# LedClock.net
KiCad netlist of a schematic drawn in EAGLE
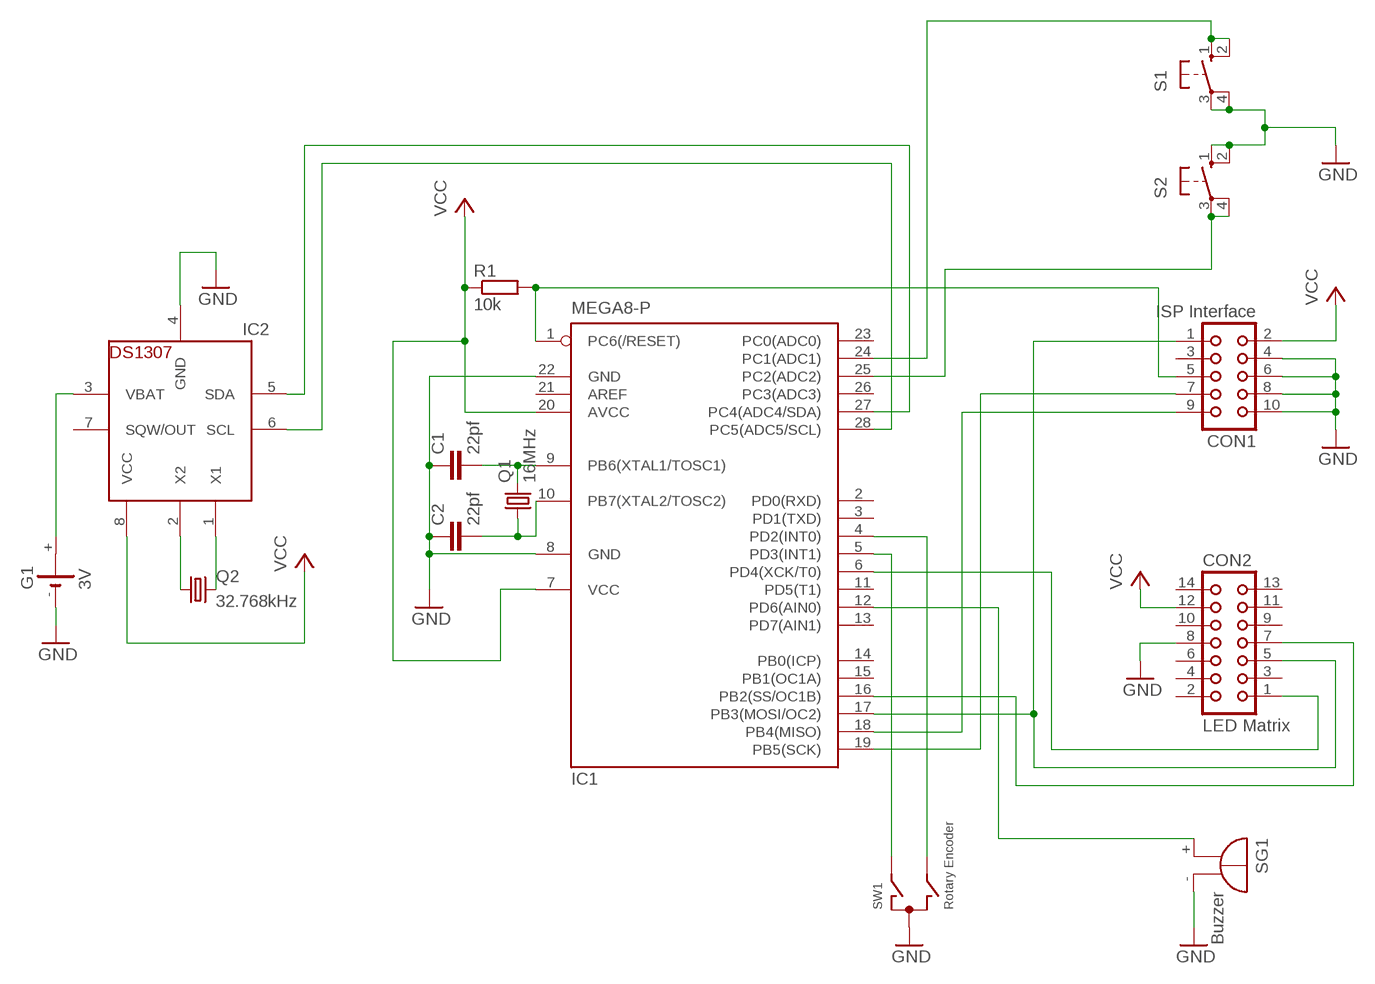
[diagram p0: schematic, sheet 1]

(export (version "E")
  (design (tool "Eeschema 10.0.6"))
  (components
    (comp (ref "C1")
      (value "22pf")
      (footprint "eagle-import:C025-025X050")
      (libsource (lib "eagle-import") (part "C-EU025-025X050"))
    )
    (comp (ref "C2")
      (value "22pf")
      (footprint "eagle-import:C025-025X050")
      (libsource (lib "eagle-import") (part "C-EU025-025X050"))
    )
    (comp (ref "CON1")
      (value "ISP Interface")
      (footprint "eagle-import:CON10")
      (libsource (lib "eagle-import") (part "CON10"))
    )
    (comp (ref "CON2")
      (value "LED Matrix")
      (footprint "eagle-import:CON14L")
      (libsource (lib "eagle-import") (part "CON14L"))
    )
    (comp (ref "G1")
      (value "3V")
      (footprint "eagle-import:CR2032H")
      (libsource (lib "eagle-import") (part "CR2032H"))
    )
    (comp (ref "IC1")
      (value "MEGA8-P")
      (footprint "eagle-import:DIL28-3")
      (libsource (lib "eagle-import") (part "MEGA8-P"))
    )
    (comp (ref "IC2")
      (value "DS1307")
      (footprint "eagle-import:DIL08")
      (libsource (lib "eagle-import") (part "DS1307"))
    )
    (comp (ref "Q1")
      (value "16MHz")
      (footprint "eagle-import:HC49_S")
      (libsource (lib "eagle-import") (part "CRYSTALHC49S"))
    )
    (comp (ref "Q2")
      (value "32.768kHz")
      (footprint "eagle-import:TC38H")
      (libsource (lib "eagle-import") (part "CRYSTALTC38H"))
    )
    (comp (ref "R1")
      (value "10k")
      (footprint "eagle-import:0207_10")
      (libsource (lib "eagle-import") (part "R-EU_0207/10"))
    )
    (comp (ref "S1")
      (value "10-XX")
      (footprint "eagle-import:B3F-10XX")
      (fields (field (name "MPN") "B3F-1000"))
      (libsource (lib "eagle-import") (part "10-XX"))
    )
    (comp (ref "S2")
      (value "10-XX")
      (footprint "eagle-import:B3F-10XX")
      (fields (field (name "MPN") "B3F-1000"))
      (libsource (lib "eagle-import") (part "10-XX"))
    )
    (comp (ref "SG1")
      (value "Buzzer")
      (footprint "eagle-import:EB2209A")
      (libsource (lib "eagle-import") (part "EB2209A"))
    )
    (comp (ref "SW1")
      (value "Rotary Encoder")
      (footprint "eagle-import:ALPS_EC12E_SW")
      (fields (field (name "MPN") "EC12E2424407"))
      (libsource (lib "eagle-import") (part "EC12E_SW"))
    )
  )
  (nets
    (net (code "1") (name "GND") (class "Default")
      (node (ref "C1") (pin "1") (pinfunction "1_1") (pintype "passive"))
      (node (ref "C2") (pin "1") (pinfunction "1_1") (pintype "passive"))
      (node (ref "CON1") (pin "10") (pinfunction "10_10") (pintype "passive"))
      (node (ref "CON1") (pin "4") (pinfunction "4_4") (pintype "passive"))
      (node (ref "CON1") (pin "6") (pinfunction "6_6") (pintype "passive"))
      (node (ref "CON1") (pin "8") (pinfunction "8_8") (pintype "passive"))
      (node (ref "CON2") (pin "8") (pinfunction "8_8") (pintype "passive"))
      (node (ref "G1") (pin "-") (pinfunction "-_-") (pintype "passive"))
      (node (ref "IC1") (pin "22") (pinfunction "GND_22") (pintype "power_in"))
      (node (ref "IC1") (pin "8") (pinfunction "GND_8") (pintype "power_in"))
      (node (ref "IC2") (pin "4") (pinfunction "GND_4") (pintype "power_in"))
      (node (ref "S1") (pin "3") (pinfunction "P_3") (pintype "passive"))
      (node (ref "S1") (pin "4") (pinfunction "P1_4") (pintype "passive"))
      (node (ref "S2") (pin "1") (pinfunction "S_1") (pintype "passive"))
      (node (ref "S2") (pin "2") (pinfunction "S1_2") (pintype "passive"))
      (node (ref "SG1") (pin "-") (pinfunction "-_-") (pintype "passive"))
      (node (ref "SW1") (pin "C") (pinfunction "C_C") (pintype "passive"))
    )
    (net (code "2") (name "Net-(IC1-PB2(SS{slash}OC1B))") (class "Default")
      (node (ref "CON2") (pin "7") (pinfunction "7_7") (pintype "passive"))
      (node (ref "IC1") (pin "16") (pinfunction "PB2(SS/OC1B)_16") (pintype "bidirectional"))
    )
    (net (code "3") (name "Net-(IC1-PB3(MOSI{slash}OC2))") (class "Default")
      (node (ref "CON1") (pin "1") (pinfunction "1_1") (pintype "passive"))
      (node (ref "CON2") (pin "5") (pinfunction "5_5") (pintype "passive"))
      (node (ref "IC1") (pin "17") (pinfunction "PB3(MOSI/OC2)_17") (pintype "bidirectional"))
    )
    (net (code "4") (name "Net-(IC1-PB4(MISO))") (class "Default")
      (node (ref "CON1") (pin "9") (pinfunction "9_9") (pintype "passive"))
      (node (ref "IC1") (pin "18") (pinfunction "PB4(MISO)_18") (pintype "bidirectional"))
    )
    (net (code "5") (name "Net-(IC1-PB5(SCK))") (class "Default")
      (node (ref "CON1") (pin "7") (pinfunction "7_7") (pintype "passive"))
      (node (ref "IC1") (pin "19") (pinfunction "PB5(SCK)_19") (pintype "bidirectional"))
    )
    (net (code "6") (name "Net-(IC1-PB6(XTAL1{slash}TOSC1))") (class "Default")
      (node (ref "C1") (pin "2") (pinfunction "2_2") (pintype "passive"))
      (node (ref "IC1") (pin "9") (pinfunction "PB6(XTAL1/TOSC1)_9") (pintype "bidirectional"))
      (node (ref "Q1") (pin "2") (pinfunction "2_2") (pintype "passive"))
    )
    (net (code "7") (name "Net-(IC1-PB7(XTAL2{slash}TOSC2))") (class "Default")
      (node (ref "C2") (pin "2") (pinfunction "2_2") (pintype "passive"))
      (node (ref "IC1") (pin "10") (pinfunction "PB7(XTAL2/TOSC2)_10") (pintype "bidirectional"))
      (node (ref "Q1") (pin "1") (pinfunction "1_1") (pintype "passive"))
    )
    (net (code "8") (name "Net-(IC1-PC1(ADC1))") (class "Default")
      (node (ref "IC1") (pin "24") (pinfunction "PC1(ADC1)_24") (pintype "bidirectional"))
      (node (ref "S1") (pin "1") (pinfunction "S_1") (pintype "passive"))
      (node (ref "S1") (pin "2") (pinfunction "S1_2") (pintype "passive"))
    )
    (net (code "9") (name "Net-(IC1-PC2(ADC2))") (class "Default")
      (node (ref "IC1") (pin "25") (pinfunction "PC2(ADC2)_25") (pintype "bidirectional"))
      (node (ref "S2") (pin "3") (pinfunction "P_3") (pintype "passive"))
      (node (ref "S2") (pin "4") (pinfunction "P1_4") (pintype "passive"))
    )
    (net (code "10") (name "Net-(IC1-PC4(ADC4{slash}SDA))") (class "Default")
      (node (ref "IC1") (pin "27") (pinfunction "PC4(ADC4/SDA)_27") (pintype "bidirectional"))
      (node (ref "IC2") (pin "5") (pinfunction "SDA_5") (pintype "bidirectional"))
    )
    (net (code "11") (name "Net-(IC1-PC5(ADC5{slash}SCL))") (class "Default")
      (node (ref "IC1") (pin "28") (pinfunction "PC5(ADC5/SCL)_28") (pintype "bidirectional"))
      (node (ref "IC2") (pin "6") (pinfunction "SCL_6") (pintype "bidirectional"))
    )
    (net (code "12") (name "Net-(IC1-PC6({slash}RESET))") (class "Default")
      (node (ref "CON1") (pin "5") (pinfunction "5_5") (pintype "passive"))
      (node (ref "IC1") (pin "1") (pinfunction "PC6(/RESET)_1") (pintype "bidirectional"))
      (node (ref "R1") (pin "2") (pinfunction "2_2") (pintype "passive"))
    )
    (net (code "13") (name "Net-(IC1-PD2(INT0))") (class "Default")
      (node (ref "IC1") (pin "4") (pinfunction "PD2(INT0)_4") (pintype "bidirectional"))
      (node (ref "SW1") (pin "B") (pinfunction "B_B") (pintype "passive"))
    )
    (net (code "14") (name "Net-(IC1-PD3(INT1))") (class "Default")
      (node (ref "IC1") (pin "5") (pinfunction "PD3(INT1)_5") (pintype "bidirectional"))
      (node (ref "SW1") (pin "A") (pinfunction "A_A") (pintype "passive"))
    )
    (net (code "15") (name "Net-(IC1-PD4(XCK{slash}T0))") (class "Default")
      (node (ref "CON2") (pin "1") (pinfunction "1_1") (pintype "passive"))
      (node (ref "IC1") (pin "6") (pinfunction "PD4(XCK/T0)_6") (pintype "bidirectional"))
    )
    (net (code "16") (name "Net-(IC1-PD6(AIN0))") (class "Default")
      (node (ref "IC1") (pin "12") (pinfunction "PD6(AIN0)_12") (pintype "bidirectional"))
      (node (ref "SG1") (pin "+") (pinfunction "+_+") (pintype "passive"))
    )
    (net (code "17") (name "Net-(IC2-VBAT)") (class "Default")
      (node (ref "G1") (pin "+") (pinfunction "+_+") (pintype "passive"))
      (node (ref "IC2") (pin "3") (pinfunction "VBAT_3") (pintype "power_in"))
    )
    (net (code "18") (name "Net-(IC2-X1)") (class "Default")
      (node (ref "IC2") (pin "1") (pinfunction "X1_1") (pintype "passive"))
      (node (ref "Q2") (pin "2") (pinfunction "2_2") (pintype "passive"))
    )
    (net (code "19") (name "Net-(IC2-X2)") (class "Default")
      (node (ref "IC2") (pin "2") (pinfunction "X2_2") (pintype "passive"))
      (node (ref "Q2") (pin "1") (pinfunction "1_1") (pintype "passive"))
    )
    (net (code "20") (name "VCC") (class "Default")
      (node (ref "CON1") (pin "2") (pinfunction "2_2") (pintype "passive"))
      (node (ref "CON2") (pin "12") (pinfunction "12_12") (pintype "passive"))
      (node (ref "IC1") (pin "20") (pinfunction "AVCC_20") (pintype "power_in"))
      (node (ref "IC1") (pin "7") (pinfunction "VCC_7") (pintype "power_in"))
      (node (ref "IC2") (pin "8") (pinfunction "VCC_8") (pintype "power_in"))
      (node (ref "R1") (pin "1") (pinfunction "1_1") (pintype "passive"))
    )
    (net (code "21") (name "unconnected-(CON1-Pad3)") (class "Default")
      (node (ref "CON1") (pin "3") (pinfunction "3_3") (pintype "passive"))
    )
    (net (code "22") (name "unconnected-(CON2-Pad2)") (class "Default")
      (node (ref "CON2") (pin "2") (pinfunction "2_2") (pintype "passive"))
    )
    (net (code "23") (name "unconnected-(CON2-Pad3)") (class "Default")
      (node (ref "CON2") (pin "3") (pinfunction "3_3") (pintype "passive"))
    )
    (net (code "24") (name "unconnected-(CON2-Pad4)") (class "Default")
      (node (ref "CON2") (pin "4") (pinfunction "4_4") (pintype "passive"))
    )
    (net (code "25") (name "unconnected-(CON2-Pad6)") (class "Default")
      (node (ref "CON2") (pin "6") (pinfunction "6_6") (pintype "passive"))
    )
    (net (code "26") (name "unconnected-(CON2-Pad9)") (class "Default")
      (node (ref "CON2") (pin "9") (pinfunction "9_9") (pintype "passive"))
    )
    (net (code "27") (name "unconnected-(CON2-Pad10)") (class "Default")
      (node (ref "CON2") (pin "10") (pinfunction "10_10") (pintype "passive"))
    )
    (net (code "28") (name "unconnected-(CON2-Pad11)") (class "Default")
      (node (ref "CON2") (pin "11") (pinfunction "11_11") (pintype "passive"))
    )
    (net (code "29") (name "unconnected-(CON2-Pad13)") (class "Default")
      (node (ref "CON2") (pin "13") (pinfunction "13_13") (pintype "passive"))
    )
    (net (code "30") (name "unconnected-(CON2-Pad14)") (class "Default")
      (node (ref "CON2") (pin "14") (pinfunction "14_14") (pintype "passive"))
    )
    (net (code "31") (name "unconnected-(G1-+-Pad+@1)") (class "Default")
      (node (ref "G1") (pin "+@1") (pinfunction "+_+@1") (pintype "passive"))
    )
    (net (code "32") (name "unconnected-(IC1-AREF-Pad21)") (class "Default")
      (node (ref "IC1") (pin "21") (pinfunction "AREF_21") (pintype "passive"))
    )
    (net (code "33") (name "unconnected-(IC1-PB0(ICP)-Pad14)") (class "Default")
      (node (ref "IC1") (pin "14") (pinfunction "PB0(ICP)_14") (pintype "bidirectional"))
    )
    (net (code "34") (name "unconnected-(IC1-PB1(OC1A)-Pad15)") (class "Default")
      (node (ref "IC1") (pin "15") (pinfunction "PB1(OC1A)_15") (pintype "bidirectional"))
    )
    (net (code "35") (name "unconnected-(IC1-PC0(ADC0)-Pad23)") (class "Default")
      (node (ref "IC1") (pin "23") (pinfunction "PC0(ADC0)_23") (pintype "bidirectional"))
    )
    (net (code "36") (name "unconnected-(IC1-PC3(ADC3)-Pad26)") (class "Default")
      (node (ref "IC1") (pin "26") (pinfunction "PC3(ADC3)_26") (pintype "bidirectional"))
    )
    (net (code "37") (name "unconnected-(IC1-PD0(RXD)-Pad2)") (class "Default")
      (node (ref "IC1") (pin "2") (pinfunction "PD0(RXD)_2") (pintype "bidirectional"))
    )
    (net (code "38") (name "unconnected-(IC1-PD1(TXD)-Pad3)") (class "Default")
      (node (ref "IC1") (pin "3") (pinfunction "PD1(TXD)_3") (pintype "bidirectional"))
    )
    (net (code "39") (name "unconnected-(IC1-PD5(T1)-Pad11)") (class "Default")
      (node (ref "IC1") (pin "11") (pinfunction "PD5(T1)_11") (pintype "bidirectional"))
    )
    (net (code "40") (name "unconnected-(IC1-PD7(AIN1)-Pad13)") (class "Default")
      (node (ref "IC1") (pin "13") (pinfunction "PD7(AIN1)_13") (pintype "bidirectional"))
    )
    (net (code "41") (name "unconnected-(IC2-SQW{slash}OUT-Pad7)") (class "Default")
      (node (ref "IC2") (pin "7") (pinfunction "SQW/OUT_7") (pintype "bidirectional"))
    )
  )
)
